# principal.net
KiCad netlist of a schematic drawn in Altium Designer
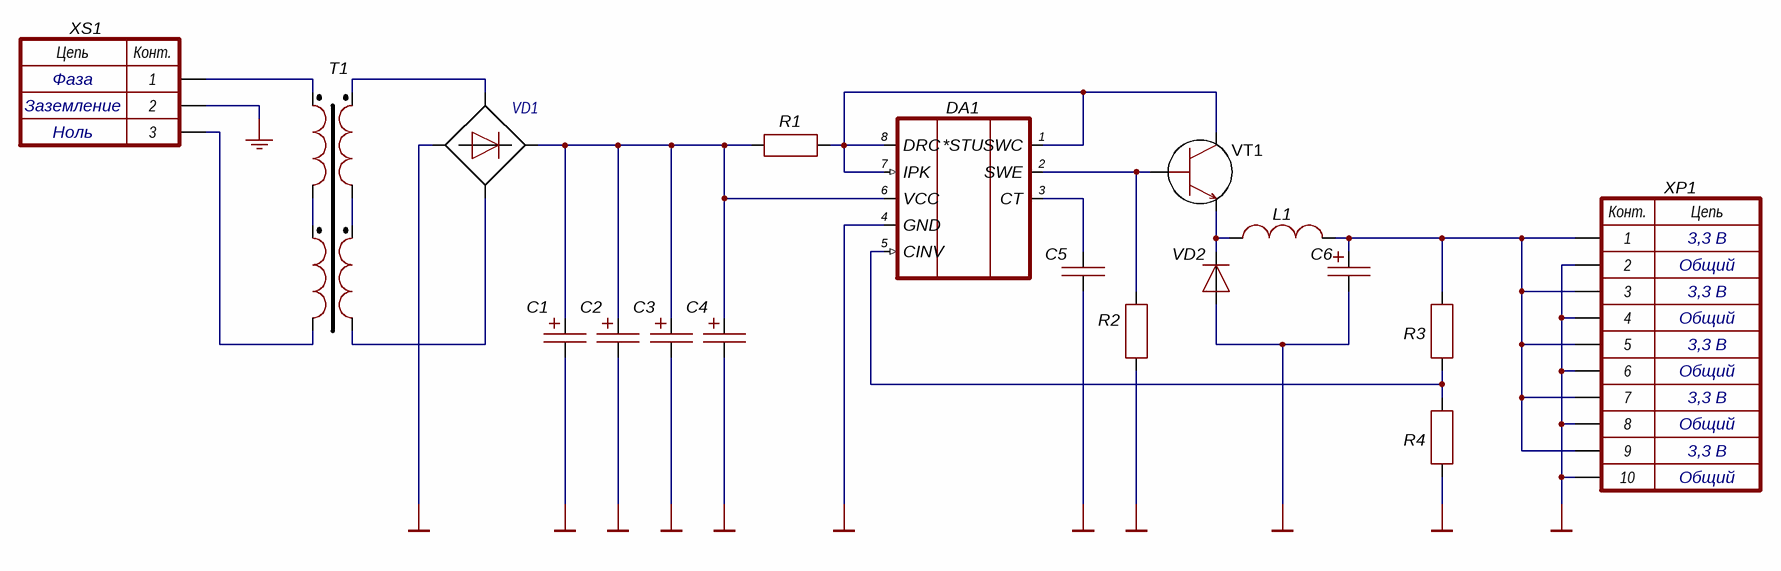
[diagram p0: principal.SchDoc]

(export (version "E")
  (design (tool "Eeschema 10.0.6"))
  (components
    (comp (ref "C1") (value "C_POL") (footprint "C_SMD_Al_G") (libsource (lib "Passive") (part "C_POL")))
    (comp (ref "C2") (value "C_POL") (footprint "C_SMD_Al_G") (libsource (lib "Passive") (part "C_POL")))
    (comp (ref "C3") (value "C_POL") (footprint "C_SMD_Al_G") (libsource (lib "Passive") (part "C_POL")))
    (comp (ref "C4") (value "C_POL") (footprint "C_SMD_Al_G") (libsource (lib "Passive") (part "C_POL")))
    (comp (ref "C5") (value "C") (footprint "C_1206") (libsource (lib "Passive") (part "C")))
    (comp (ref "C6") (value "C_POL") (footprint "C_SMD_Al_G") (libsource (lib "Passive") (part "C_POL")))
    (comp (ref "DA1") (value "MC34063") (footprint "SO8") (libsource (lib "IC") (part "MC34063")))
    (comp (ref "L1") (value "L") (footprint "IND_HTTI-220-3.0") (libsource (lib "Passive") (part "L")))
    (comp (ref "R1") (value "R") (footprint "R_1206") (libsource (lib "Passive") (part "R")))
    (comp (ref "R2") (value "R") (footprint "R_1206") (libsource (lib "Passive") (part "R")))
    (comp (ref "R3") (value "R") (footprint "R_1206") (libsource (lib "Passive") (part "R")))
    (comp (ref "R4") (value "R") (footprint "R_1206") (libsource (lib "Passive") (part "R")))
    (comp (ref "T1")
      (value "T1-6_12-10")
      (footprint "TRANSFORMER_FS24-1500")
      (libsource (lib "Passive") (part "T1-6_12-10"))
    )
    (comp (ref "VD1") (value "DB201S") (footprint "DIOB_DB107S") (libsource (lib "library") (part "DB201S")))
    (comp (ref "VD2") (value "VD") (footprint "SOD123") (libsource (lib "VD") (part "VD")))
    (comp (ref "VT1")
      (value "NPN_BEC")
      (footprint "TO229P990X238-3N")
      (libsource (lib "VT") (part "NPN_BEC"))
    )
    (comp (ref "XP1") (value "X_10") (footprint "PLS-10") (libsource (lib "Connectors") (part "X_10")))
    (comp (ref "XS1") (value "X_3") (footprint "PCBComponent_1") (libsource (lib "library") (part "X_3")))
  )
  (nets
    (net (code "1") (name "EARTH") (class "Default")
      (node (ref "XS1") (pin "2") (pinfunction "2_2") (pintype "passive"))
    )
    (net (code "2") (name "GND") (class "Default")
      (node (ref "C1") (pin "1") (pinfunction "1_1") (pintype "passive"))
      (node (ref "C2") (pin "1") (pinfunction "1_1") (pintype "passive"))
      (node (ref "C3") (pin "1") (pinfunction "1_1") (pintype "passive"))
      (node (ref "C4") (pin "1") (pinfunction "1_1") (pintype "passive"))
      (node (ref "C5") (pin "1") (pinfunction "1_1") (pintype "passive"))
      (node (ref "C6") (pin "1") (pinfunction "1_1") (pintype "passive"))
      (node (ref "DA1") (pin "4") (pinfunction "GND_4") (pintype "power_in"))
      (node (ref "R2") (pin "1") (pinfunction "1_1") (pintype "passive"))
      (node (ref "R4") (pin "1") (pinfunction "1_1") (pintype "passive"))
      (node (ref "VD1") (pin "NEG") (pinfunction "A_NEG") (pintype "passive"))
      (node (ref "VD2") (pin "1") (pinfunction "A_1") (pintype "passive"))
      (node (ref "XP1") (pin "10") (pintype "passive"))
      (node (ref "XP1") (pin "2") (pintype "passive"))
      (node (ref "XP1") (pin "4") (pintype "passive"))
      (node (ref "XP1") (pin "6") (pintype "passive"))
      (node (ref "XP1") (pin "8") (pintype "passive"))
    )
    (net (code "3") (name "Net-(C6-Pad2)") (class "Default")
      (node (ref "C6") (pin "2") (pinfunction "2_2") (pintype "passive"))
      (node (ref "L1") (pin "2") (pinfunction "2_2") (pintype "passive"))
      (node (ref "R3") (pin "2") (pinfunction "2_2") (pintype "passive"))
      (node (ref "XP1") (pin "1") (pintype "passive"))
      (node (ref "XP1") (pin "3") (pintype "passive"))
      (node (ref "XP1") (pin "5") (pintype "passive"))
      (node (ref "XP1") (pin "7") (pintype "passive"))
      (node (ref "XP1") (pin "9") (pintype "passive"))
    )
    (net (code "4") (name "Net-(DA1-CINV)") (class "Default")
      (node (ref "DA1") (pin "5") (pinfunction "CINV_5") (pintype "input"))
      (node (ref "R3") (pin "1") (pinfunction "1_1") (pintype "passive"))
      (node (ref "R4") (pin "2") (pinfunction "2_2") (pintype "passive"))
    )
    (net (code "5") (name "Net-(DA1-CT)") (class "Default")
      (node (ref "C5") (pin "2") (pinfunction "2_2") (pintype "passive"))
      (node (ref "DA1") (pin "3") (pinfunction "CT_3") (pintype "passive"))
    )
    (net (code "6") (name "Net-(DA1-DRC)") (class "Default")
      (node (ref "DA1") (pin "1") (pinfunction "SWC_1") (pintype "power_in"))
      (node (ref "DA1") (pin "7") (pinfunction "IPK_7") (pintype "input"))
      (node (ref "DA1") (pin "8") (pinfunction "DRC_8") (pintype "power_in"))
      (node (ref "R1") (pin "1") (pinfunction "1_1") (pintype "passive"))
      (node (ref "VT1") (pin "3") (pinfunction "c_3") (pintype "passive"))
    )
    (net (code "7") (name "Net-(DA1-SWE)") (class "Default")
      (node (ref "DA1") (pin "2") (pinfunction "SWE_2") (pintype "power_in"))
      (node (ref "R2") (pin "2") (pinfunction "2_2") (pintype "passive"))
      (node (ref "VT1") (pin "1") (pinfunction "b_1") (pintype "passive"))
    )
    (net (code "8") (name "Net-(DA1-VCC)") (class "Default")
      (node (ref "C1") (pin "2") (pinfunction "2_2") (pintype "passive"))
      (node (ref "C2") (pin "2") (pinfunction "2_2") (pintype "passive"))
      (node (ref "C3") (pin "2") (pinfunction "2_2") (pintype "passive"))
      (node (ref "C4") (pin "2") (pinfunction "2_2") (pintype "passive"))
      (node (ref "DA1") (pin "6") (pinfunction "VCC_6") (pintype "power_in"))
      (node (ref "R1") (pin "2") (pinfunction "2_2") (pintype "passive"))
      (node (ref "VD1") (pin "POS") (pinfunction "C_POS") (pintype "passive"))
    )
    (net (code "9") (name "Net-(T1-1-Pad2)") (class "Default")
      (node (ref "T1") (pin "2") (pinfunction "1_2") (pintype "passive"))
      (node (ref "T1") (pin "3") (pinfunction "6_3") (pintype "passive"))
    )
    (net (code "10") (name "Net-(T1-1-Pad4)") (class "Default")
      (node (ref "T1") (pin "4") (pinfunction "1_4") (pintype "passive"))
      (node (ref "XS1") (pin "1") (pinfunction "1_1") (pintype "passive"))
    )
    (net (code "11") (name "Net-(T1-6-Pad1)") (class "Default")
      (node (ref "T1") (pin "1") (pinfunction "6_1") (pintype "passive"))
      (node (ref "XS1") (pin "3") (pinfunction "3_3") (pintype "passive"))
    )
    (net (code "12") (name "Net-(T1-10-Pad6)") (class "Default")
      (node (ref "T1") (pin "6") (pinfunction "10_6") (pintype "passive"))
      (node (ref "T1") (pin "7") (pinfunction "12_7") (pintype "passive"))
    )
    (net (code "13") (name "Net-(VD1-B)") (class "Default")
      (node (ref "T1") (pin "5") (pinfunction "12_5") (pintype "passive"))
      (node (ref "VD1") (pin "1") (pinfunction "B_1") (pintype "passive"))
    )
    (net (code "14") (name "Net-(VD1-D)") (class "Default")
      (node (ref "T1") (pin "8") (pinfunction "10_8") (pintype "passive"))
      (node (ref "VD1") (pin "2") (pinfunction "D_2") (pintype "passive"))
    )
    (net (code "15") (name "Net-(VD2-C)") (class "Default")
      (node (ref "L1") (pin "1") (pinfunction "1_1") (pintype "passive"))
      (node (ref "VD2") (pin "2") (pinfunction "C_2") (pintype "passive"))
      (node (ref "VT1") (pin "2") (pinfunction "e_2") (pintype "passive"))
    )
  )
)
